# STEP_DOWN.net
KiCad netlist of a schematic drawn in Altium Designer
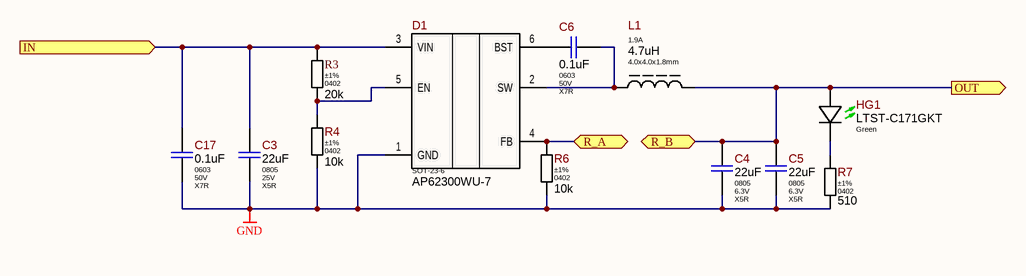
[diagram p0: STEP_DOWN.SchDoc]

(export (version "E")
  (design (tool "Eeschema 10.0.6"))
  (components
    (comp (ref "C3")
      (value "22uF")
      (footprint "CAP-0805(2012)X125T20")
      (description "22uF 25V X5R ±20% 0805 Ceramic Capacitor RoHS")
      (fields
        (field (name "PACKAGE") "0805")
        (field (name "VOLTAGE") "25V")
        (field (name "DIELECTRIC TYPE") "X5R")
        (field (name "PART NUMBER") "CL21A226MAYNNNE")
        (field (name "MANUFACTURER") "Samsung Electro-Mechanics")
      )
      (libsource (lib "AjaxLibrary") (part "Capacitor-NonPolar"))
    )
    (comp (ref "C4")
      (value "22uF")
      (footprint "C_CERAMIC_0805_MED")
      (description "22uF 6.3V X5R ±20% 0805 Ceramic Capacitor RoHS")
      (fields
        (field (name "PACKAGE") "0805")
        (field (name "VOLTAGE") "6.3V")
        (field (name "DIELECTRIC TYPE") "X5R")
        (field (name "PART NUMBER") "GRM21BR60J226ME39L")
        (field (name "MANUFACTURER") "Murata Electronics")
      )
      (libsource (lib "AjaxLibrary") (part "Capacitor-NonPolar"))
    )
    (comp (ref "C5")
      (value "22uF")
      (footprint "C_CERAMIC_0805_MED")
      (description "22uF 6.3V X5R ±20% 0805 Ceramic Capacitor RoHS")
      (fields
        (field (name "PACKAGE") "0805")
        (field (name "VOLTAGE") "6.3V")
        (field (name "DIELECTRIC TYPE") "X5R")
        (field (name "PART NUMBER") "GRM21BR60J226ME39L")
        (field (name "MANUFACTURER") "Murata Electronics")
      )
      (libsource (lib "AjaxLibrary") (part "Capacitor-NonPolar"))
    )
    (comp (ref "C6")
      (value "0.1uF")
      (footprint "C_CERAMIC_0603_MED")
      (description "100nF 50V X7R ±10% 0603 Ceramic Capacitor RoHS")
      (fields
        (field (name "PACKAGE") "0603")
        (field (name "VOLTAGE") "50V")
        (field (name "DIELECTRIC TYPE") "X7R")
        (field (name "PART NUMBER") "CL10B104KB8NNND")
        (field (name "MANUFACTURER") "Samsung Electro-Mechanics")
      )
      (libsource (lib "capacitors") (part "CL10B104KB8NNND"))
    )
    (comp (ref "C17")
      (value "0.1uF")
      (footprint "C_CERAMIC_0603_MED")
      (description "100nF 50V X7R ±10% 0603 Ceramic Capacitor RoHS")
      (fields
        (field (name "PACKAGE") "0603")
        (field (name "VOLTAGE") "50V")
        (field (name "DIELECTRIC TYPE") "X7R")
        (field (name "PART NUMBER") "CL10B104KB8NNND")
        (field (name "MANUFACTURER") "Samsung Electro-Mechanics")
      )
      (libsource (lib "capacitors") (part "CL10B104KB8NNND"))
    )
    (comp (ref "D1")
      (value "AP62300WU-7")
      (footprint "SOT-23-6")
      (description "4.35V to 18V, 2A, High Efficiency Synchronous Step Down Converter, 500kHz, SOT-23-6")
      (fields
        (field (name "MANUFACTURER") "Diodes Incorporated")
        (field (name "PACKAGE") "SOT-23-6")
        (field (name "PART NUMBER") "AP62300WU-7")
      )
      (libsource (lib "CAMLIB") (part "AP62300WU-7"))
    )
    (comp (ref "HG1")
      (value "LTST-C171GKT")
      (footprint "LTST-C171GKT")
      (description "Low Power LED, Green 565nm, Clear, SMD 0805, Vf 2.1V - 2.6V, 5 ~ 12mcd @ 20 mA, 130°")
      (fields
        (field (name "PART NUMBER") "LTST-C171GKT")
        (field (name "COLOR") "Green")
        (field (name "MANUFACTURER") "Lite-On Optoelectronics")
      )
      (libsource (lib "AjaxLibrary") (part "LED-Green"))
    )
    (comp (ref "L1")
      (value "4.7uH")
      (footprint "SRN4018-Series_1.8mm")
      (description "4.7uH Semi-Shielded Wirewound Inductor 1.9A 84mOhm Max")
      (fields
        (field (name "CURRENT") "1.9A")
        (field (name "PACKAGE") "4.0x4.0x1.8mm")
        (field (name "PART NUMBER") "SRN4018-4R7M")
        (field (name "TOLERANCE") "±20%")
      )
      (libsource (lib "AjaxLibrary") (part "Inductor-Ferrite-Fixed"))
    )
    (comp (ref "R3")
      (value "20k")
      (footprint "R_ANY_CHIP_0402_MED")
      (description "20 kOhms ±1% 1/16W 0402 Thick Film Resistor")
      (fields
        (field (name "TOLERANCE") "±1%")
        (field (name "PACKAGE") "0402")
        (field (name "PART NUMBER") "RC0402FR-0720KL")
        (field (name "MANUFACTURER") "Yageo")
      )
      (libsource (lib "AjaxLibrary") (part "Resistor"))
    )
    (comp (ref "R4")
      (value "10k")
      (footprint "R_ANY_CHIP_0402_MED")
      (description "10 kOhms ±1% 1/16W 0402 Thick Film Resistor")
      (fields
        (field (name "TOLERANCE") "±1%")
        (field (name "PACKAGE") "0402")
        (field (name "PART NUMBER") "RC0402FR-0710KL")
        (field (name "MANUFACTURER") "Yageo")
      )
      (libsource (lib "AjaxLibrary") (part "Resistor"))
    )
    (comp (ref "R6")
      (value "10k")
      (footprint "R_ANY_CHIP_0402_MED")
      (description "10 kOhms ±1% 1/16W 0402 Thick Film Resistor")
      (fields
        (field (name "TOLERANCE") "±1%")
        (field (name "PACKAGE") "0402")
        (field (name "PART NUMBER") "RC0402FR-0710KL")
        (field (name "MANUFACTURER") "Yageo")
      )
      (libsource (lib "AjaxLibrary") (part "Resistor"))
    )
    (comp (ref "R7")
      (value "510")
      (footprint "R_ANY_CHIP_0402_MED")
      (description "510 Ohms ±1% 1/16W 0402 Thick Film Resistor")
      (fields
        (field (name "TOLERANCE") "±1%")
        (field (name "PACKAGE") "0402")
        (field (name "PART NUMBER") "RC0402FR-07510RL")
        (field (name "MANUFACTURER") "Yageo")
      )
      (libsource (lib "AjaxLibrary") (part "Resistor"))
    )
  )
  (nets
    (net (code "1") (name "/IN") (class "Default")
      (node (ref "C17") (pin "2") (pinfunction "2_2") (pintype "passive"))
      (node (ref "C3") (pin "1") (pinfunction "1_1") (pintype "passive"))
      (node (ref "D1") (pin "3") (pinfunction "VIN_3") (pintype "passive"))
      (node (ref "R3") (pin "1") (pintype "passive"))
    )
    (net (code "2") (name "/OUT") (class "Default")
      (node (ref "C4") (pin "1") (pinfunction "1_1") (pintype "passive"))
      (node (ref "C5") (pin "1") (pinfunction "1_1") (pintype "passive"))
      (node (ref "HG1") (pin "AN") (pinfunction "Anode_AN") (pintype "passive"))
      (node (ref "L1") (pin "2") (pintype "passive"))
    )
    (net (code "3") (name "/R_A") (class "Default")
      (node (ref "D1") (pin "4") (pinfunction "FB_4") (pintype "passive"))
      (node (ref "R6") (pin "1") (pintype "passive"))
    )
    (net (code "4") (name "GND") (class "Default")
      (node (ref "C17") (pin "1") (pinfunction "1_1") (pintype "passive"))
      (node (ref "C3") (pin "2") (pinfunction "2_2") (pintype "passive"))
      (node (ref "C4") (pin "2") (pinfunction "2_2") (pintype "passive"))
      (node (ref "C5") (pin "2") (pinfunction "2_2") (pintype "passive"))
      (node (ref "D1") (pin "1") (pinfunction "GND_1") (pintype "passive"))
      (node (ref "R4") (pin "2") (pintype "passive"))
      (node (ref "R6") (pin "2") (pintype "passive"))
      (node (ref "R7") (pin "1") (pintype "passive"))
    )
    (net (code "5") (name "Net-(D1-BST)") (class "Default")
      (node (ref "C6") (pin "2") (pinfunction "2_2") (pintype "passive"))
      (node (ref "D1") (pin "6") (pinfunction "BST_6") (pintype "passive"))
    )
    (net (code "6") (name "Net-(D1-EN)") (class "Default")
      (node (ref "D1") (pin "5") (pinfunction "EN_5") (pintype "passive"))
      (node (ref "R3") (pin "2") (pintype "passive"))
      (node (ref "R4") (pin "1") (pintype "passive"))
    )
    (net (code "7") (name "Net-(D1-SW)") (class "Default")
      (node (ref "C6") (pin "1") (pinfunction "1_1") (pintype "passive"))
      (node (ref "D1") (pin "2") (pinfunction "SW_2") (pintype "passive"))
      (node (ref "L1") (pin "1") (pintype "passive"))
    )
    (net (code "8") (name "Net-(HG1-Cathode)") (class "Default")
      (node (ref "HG1") (pin "CA") (pinfunction "Cathode_CA") (pintype "passive"))
      (node (ref "R7") (pin "2") (pintype "passive"))
    )
  )
)
